# Spring2020V1_3.net
KiCad netlist of a schematic drawn in EAGLE
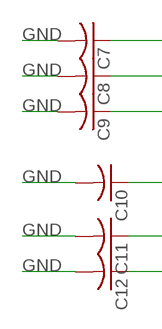
[diagram p0: schematic, sheet 1, part 1 of 2]
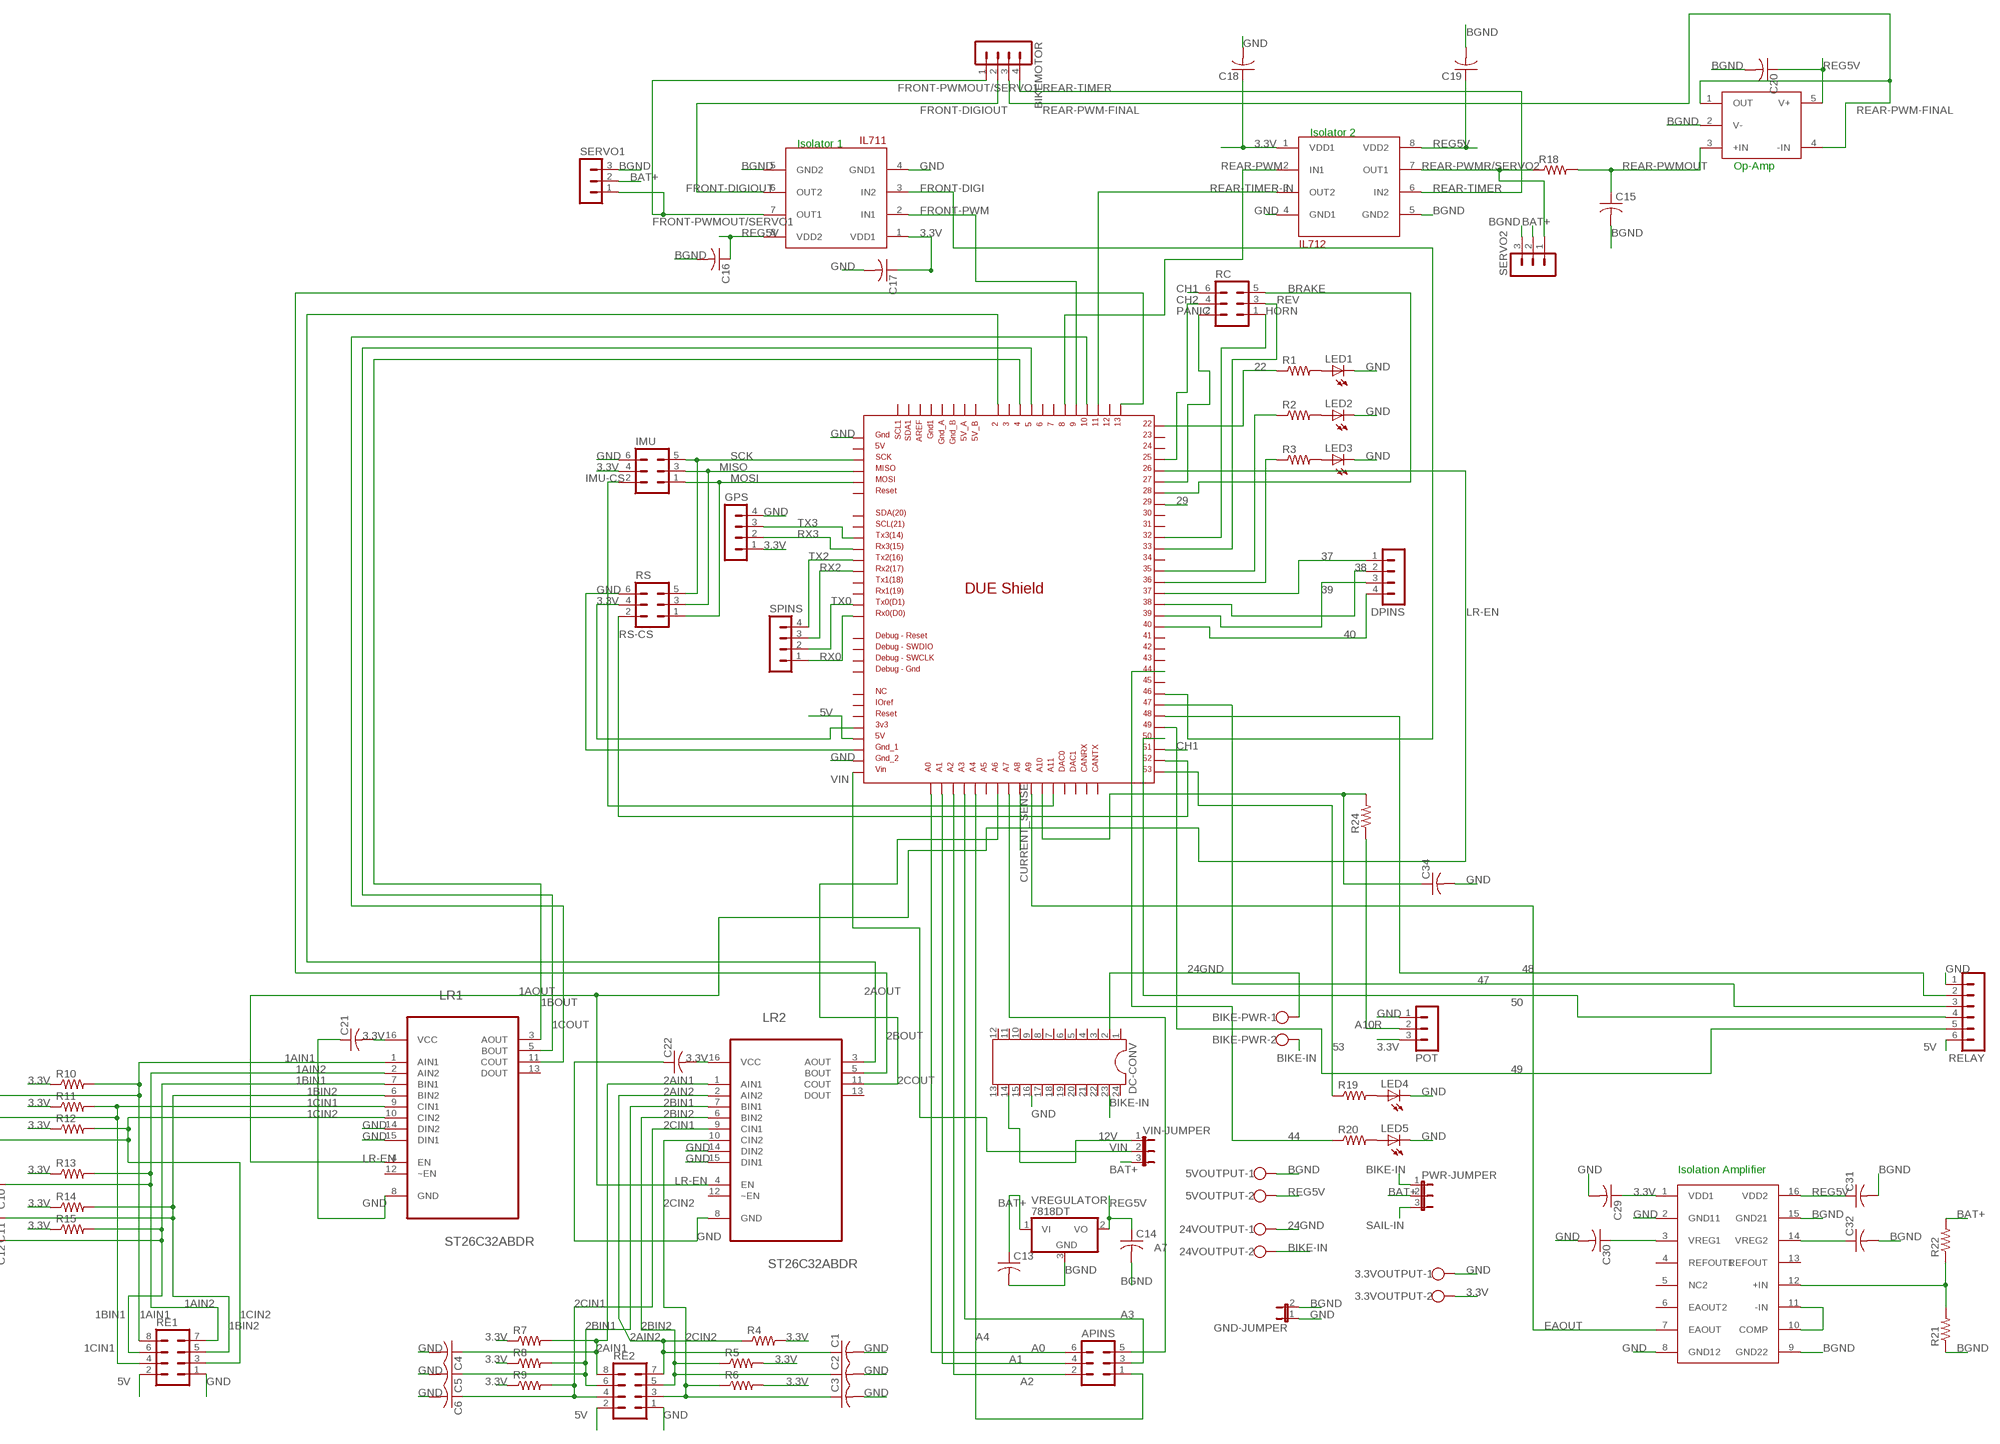
[diagram p1: schematic, sheet 1, part 2 of 2]

(export (version "E")
  (design (tool "Eeschema 10.0.6"))
  (components
    (comp (ref "3.3VOUTPUT")
      (value "W237-102")
      (footprint "eagle-import:W237-102")
      (fields (field (name "MPN") "237-102"))
      (libsource (lib "eagle-import") (part "W237-102"))
    )
    (comp (ref "5VOUTPUT")
      (value "W237-102")
      (footprint "eagle-import:W237-102")
      (fields (field (name "MPN") "237-102"))
      (libsource (lib "eagle-import") (part "W237-102"))
    )
    (comp (ref "24VOUTPUT")
      (value "W237-102")
      (footprint "eagle-import:W237-102")
      (fields (field (name "MPN") "237-102"))
      (libsource (lib "eagle-import") (part "W237-102"))
    )
    (comp (ref "APINS")
      (value "MA03-2")
      (footprint "eagle-import:MA03-2")
      (libsource (lib "eagle-import") (part "MA03-2"))
    )
    (comp (ref "BIKE-PWR")
      (value "W237-102")
      (footprint "eagle-import:W237-102")
      (fields (field (name "MPN") "237-102"))
      (libsource (lib "eagle-import") (part "W237-102"))
    )
    (comp (ref "BIKEMOTOR")
      (value "MA04-1")
      (footprint "eagle-import:MA04-1")
      (libsource (lib "eagle-import") (part "MA04-1"))
    )
    (comp (ref "C1")
      (value "C-US025-025X050")
      (footprint "eagle-import:C025-025X050")
      (libsource (lib "eagle-import") (part "C-US025-025X050"))
    )
    (comp (ref "C2")
      (value "C-US025-025X050")
      (footprint "eagle-import:C025-025X050")
      (libsource (lib "eagle-import") (part "C-US025-025X050"))
    )
    (comp (ref "C3")
      (value "C-US025-025X050")
      (footprint "eagle-import:C025-025X050")
      (libsource (lib "eagle-import") (part "C-US025-025X050"))
    )
    (comp (ref "C4")
      (value "C-US025-025X050")
      (footprint "eagle-import:C025-025X050")
      (libsource (lib "eagle-import") (part "C-US025-025X050"))
    )
    (comp (ref "C5")
      (value "C-US025-025X050")
      (footprint "eagle-import:C025-025X050")
      (libsource (lib "eagle-import") (part "C-US025-025X050"))
    )
    (comp (ref "C6")
      (value "C-US025-025X050")
      (footprint "eagle-import:C025-025X050")
      (libsource (lib "eagle-import") (part "C-US025-025X050"))
    )
    (comp (ref "C7")
      (value "C-US025-025X050")
      (footprint "eagle-import:C025-025X050")
      (libsource (lib "eagle-import") (part "C-US025-025X050"))
    )
    (comp (ref "C8")
      (value "C-US025-025X050")
      (footprint "eagle-import:C025-025X050")
      (libsource (lib "eagle-import") (part "C-US025-025X050"))
    )
    (comp (ref "C9")
      (value "C-US025-025X050")
      (footprint "eagle-import:C025-025X050")
      (libsource (lib "eagle-import") (part "C-US025-025X050"))
    )
    (comp (ref "C10")
      (value "C-US025-025X050")
      (footprint "eagle-import:C025-025X050")
      (libsource (lib "eagle-import") (part "C-US025-025X050"))
    )
    (comp (ref "C11")
      (value "C-US025-025X050")
      (footprint "eagle-import:C025-025X050")
      (libsource (lib "eagle-import") (part "C-US025-025X050"))
    )
    (comp (ref "C12")
      (value "C-US025-025X050")
      (footprint "eagle-import:C025-025X050")
      (libsource (lib "eagle-import") (part "C-US025-025X050"))
    )
    (comp (ref "C13")
      (value "C-US025-050X050")
      (footprint "eagle-import:C025-050X050")
      (libsource (lib "eagle-import") (part "C-US025-050X050"))
    )
    (comp (ref "C14")
      (value "C-US025-050X050")
      (footprint "eagle-import:C025-050X050")
      (libsource (lib "eagle-import") (part "C-US025-050X050"))
    )
    (comp (ref "C15")
      (value "C-US025-050X050")
      (footprint "eagle-import:C025-050X050")
      (libsource (lib "eagle-import") (part "C-US025-050X050"))
    )
    (comp (ref "C16")
      (value "C-US025-050X050")
      (footprint "eagle-import:C025-050X050")
      (libsource (lib "eagle-import") (part "C-US025-050X050"))
    )
    (comp (ref "C17")
      (value "C-US025-050X050")
      (footprint "eagle-import:C025-050X050")
      (libsource (lib "eagle-import") (part "C-US025-050X050"))
    )
    (comp (ref "C18")
      (value "C-US025-050X050")
      (footprint "eagle-import:C025-050X050")
      (libsource (lib "eagle-import") (part "C-US025-050X050"))
    )
    (comp (ref "C19")
      (value "C-US025-050X050")
      (footprint "eagle-import:C025-050X050")
      (libsource (lib "eagle-import") (part "C-US025-050X050"))
    )
    (comp (ref "C20")
      (value "C-US025-050X050")
      (footprint "eagle-import:C025-050X050")
      (libsource (lib "eagle-import") (part "C-US025-050X050"))
    )
    (comp (ref "C21")
      (value "C-US025-050X050")
      (footprint "eagle-import:C025-050X050")
      (libsource (lib "eagle-import") (part "C-US025-050X050"))
    )
    (comp (ref "C22")
      (value "C-US025-050X050")
      (footprint "eagle-import:C025-050X050")
      (libsource (lib "eagle-import") (part "C-US025-050X050"))
    )
    (comp (ref "C29")
      (value "C-US025-050X050")
      (footprint "eagle-import:C025-050X050")
      (libsource (lib "eagle-import") (part "C-US025-050X050"))
    )
    (comp (ref "C30")
      (value "C-US025-050X050")
      (footprint "eagle-import:C025-050X050")
      (libsource (lib "eagle-import") (part "C-US025-050X050"))
    )
    (comp (ref "C31")
      (value "C-US025-050X050")
      (footprint "eagle-import:C025-050X050")
      (libsource (lib "eagle-import") (part "C-US025-050X050"))
    )
    (comp (ref "C32")
      (value "C-US025-050X050")
      (footprint "eagle-import:C025-050X050")
      (libsource (lib "eagle-import") (part "C-US025-050X050"))
    )
    (comp (ref "C34")
      (value "C-US025-050X050")
      (footprint "eagle-import:C025-050X050")
      (libsource (lib "eagle-import") (part "C-US025-050X050"))
    )
    (comp (ref "DC-CONV")
      (value "CU.INC---VAWQ6-Q48-S12H-6")
      (footprint "eagle-import:DIL24-6")
      (libsource (lib "eagle-import") (part "CU.INC---VAWQ6-Q48-S12H-6"))
    )
    (comp (ref "DPINS")
      (value "MA04-1")
      (footprint "eagle-import:MA04-1")
      (libsource (lib "eagle-import") (part "MA04-1"))
    )
    (comp (ref "GND-JUMPER")
      (value "JP1E")
      (footprint "eagle-import:JP1")
      (libsource (lib "eagle-import") (part "JP1E"))
    )
    (comp (ref "GPS")
      (value "MA04-1")
      (footprint "eagle-import:MA04-1")
      (libsource (lib "eagle-import") (part "MA04-1"))
    )
    (comp (ref "IMU")
      (value "MA03-2")
      (footprint "eagle-import:MA03-2")
      (libsource (lib "eagle-import") (part "MA03-2"))
    )
    (comp (ref "LED1")
      (value "LED5MM")
      (footprint "eagle-import:LED5MM")
      (libsource (lib "eagle-import") (part "LED5MM"))
    )
    (comp (ref "LED2")
      (value "LED5MM")
      (footprint "eagle-import:LED5MM")
      (libsource (lib "eagle-import") (part "LED5MM"))
    )
    (comp (ref "LED3")
      (value "LED5MM")
      (footprint "eagle-import:LED5MM")
      (libsource (lib "eagle-import") (part "LED5MM"))
    )
    (comp (ref "LED4")
      (value "LED5MM")
      (footprint "eagle-import:LED5MM")
      (libsource (lib "eagle-import") (part "LED5MM"))
    )
    (comp (ref "LED5")
      (value "LED5MM")
      (footprint "eagle-import:LED5MM")
      (libsource (lib "eagle-import") (part "LED5MM"))
    )
    (comp (ref "LR1")
      (value "ST26C32ABDR")
      (footprint "eagle-import:SOIC127P600X175-16N")
      (libsource (lib "eagle-import") (part "ST26C32ABDR"))
    )
    (comp (ref "LR2")
      (value "ST26C32ABDR")
      (footprint "eagle-import:SOIC127P600X175-16N")
      (libsource (lib "eagle-import") (part "ST26C32ABDR"))
    )
    (comp (ref "OP-AMP")
      (value "OPAMP")
      (footprint "eagle-import:SOT95P280X145-5N")
      (libsource (lib "eagle-import") (part "OPAMP"))
    )
    (comp (ref "POT")
      (value "MA03-1")
      (footprint "eagle-import:MA03-1")
      (libsource (lib "eagle-import") (part "MA03-1"))
    )
    (comp (ref "PWR-JUMPER")
      (value "JP2E")
      (footprint "eagle-import:JP2")
      (libsource (lib "eagle-import") (part "JP2E"))
    )
    (comp (ref "R1")
      (value "R-US_0309/10")
      (footprint "eagle-import:0309_10")
      (libsource (lib "eagle-import") (part "R-US_0309/10"))
    )
    (comp (ref "R2")
      (value "R-US_0309/10")
      (footprint "eagle-import:0309_10")
      (libsource (lib "eagle-import") (part "R-US_0309/10"))
    )
    (comp (ref "R3")
      (value "R-US_0309/10")
      (footprint "eagle-import:0309_10")
      (libsource (lib "eagle-import") (part "R-US_0309/10"))
    )
    (comp (ref "R4")
      (value "R-US_0613/15")
      (footprint "eagle-import:P0613_15")
      (libsource (lib "eagle-import") (part "resistor_R-US_0613/15"))
    )
    (comp (ref "R5")
      (value "R-US_0613/15")
      (footprint "eagle-import:P0613_15")
      (libsource (lib "eagle-import") (part "resistor_R-US_0613/15"))
    )
    (comp (ref "R6")
      (value "R-US_0613/15")
      (footprint "eagle-import:P0613_15")
      (libsource (lib "eagle-import") (part "resistor_R-US_0613/15"))
    )
    (comp (ref "R7")
      (value "R-US_0613/15")
      (footprint "eagle-import:P0613_15")
      (libsource (lib "eagle-import") (part "resistor_R-US_0613/15"))
    )
    (comp (ref "R8")
      (value "R-US_0613/15")
      (footprint "eagle-import:P0613_15")
      (libsource (lib "eagle-import") (part "resistor_R-US_0613/15"))
    )
    (comp (ref "R9")
      (value "R-US_0613/15")
      (footprint "eagle-import:P0613_15")
      (libsource (lib "eagle-import") (part "resistor_R-US_0613/15"))
    )
    (comp (ref "R10")
      (value "R-US_0613/15")
      (footprint "eagle-import:P0613_15")
      (libsource (lib "eagle-import") (part "resistor_R-US_0613/15"))
    )
    (comp (ref "R11")
      (value "R-US_0613/15")
      (footprint "eagle-import:P0613_15")
      (libsource (lib "eagle-import") (part "resistor_R-US_0613/15"))
    )
    (comp (ref "R12")
      (value "R-US_0613/15")
      (footprint "eagle-import:P0613_15")
      (libsource (lib "eagle-import") (part "resistor_R-US_0613/15"))
    )
    (comp (ref "R13")
      (value "R-US_0613/15")
      (footprint "eagle-import:P0613_15")
      (libsource (lib "eagle-import") (part "resistor_R-US_0613/15"))
    )
    (comp (ref "R14")
      (value "R-US_0613/15")
      (footprint "eagle-import:P0613_15")
      (libsource (lib "eagle-import") (part "resistor_R-US_0613/15"))
    )
    (comp (ref "R15")
      (value "R-US_0613/15")
      (footprint "eagle-import:P0613_15")
      (libsource (lib "eagle-import") (part "resistor_R-US_0613/15"))
    )
    (comp (ref "R18")
      (value "R-US_0414/15")
      (footprint "eagle-import:0414_15")
      (libsource (lib "eagle-import") (part "resistor_R-US_0414/15"))
    )
    (comp (ref "R19")
      (value "R-US_0309/10")
      (footprint "eagle-import:0309_10")
      (libsource (lib "eagle-import") (part "R-US_0309/10"))
    )
    (comp (ref "R20")
      (value "R-US_0309/10")
      (footprint "eagle-import:0309_10")
      (libsource (lib "eagle-import") (part "R-US_0309/10"))
    )
    (comp (ref "R21")
      (value "R-US_0414/15")
      (footprint "eagle-import:0414_15")
      (libsource (lib "eagle-import") (part "resistor_R-US_0414/15"))
    )
    (comp (ref "R22")
      (value "R-US_0414/15")
      (footprint "eagle-import:0414_15")
      (libsource (lib "eagle-import") (part "resistor_R-US_0414/15"))
    )
    (comp (ref "R24")
      (value "R-US_0414/15")
      (footprint "eagle-import:0414_15")
      (libsource (lib "eagle-import") (part "resistor_R-US_0414/15"))
    )
    (comp (ref "RC")
      (value "MA03-2")
      (footprint "eagle-import:MA03-2")
      (libsource (lib "eagle-import") (part "MA03-2"))
    )
    (comp (ref "RE1")
      (value "MA04-2")
      (footprint "eagle-import:MA04-2")
      (libsource (lib "eagle-import") (part "MA04-2"))
    )
    (comp (ref "RE2")
      (value "MA04-2")
      (footprint "eagle-import:MA04-2")
      (libsource (lib "eagle-import") (part "MA04-2"))
    )
    (comp (ref "RELAY")
      (value "MA06-1")
      (footprint "eagle-import:MA06-1")
      (libsource (lib "eagle-import") (part "MA06-1"))
    )
    (comp (ref "RS")
      (value "MA03-2")
      (footprint "eagle-import:MA03-2")
      (libsource (lib "eagle-import") (part "MA03-2"))
    )
    (comp (ref "SERVO1")
      (value "MA03-1")
      (footprint "eagle-import:MA03-1")
      (libsource (lib "eagle-import") (part "MA03-1"))
    )
    (comp (ref "SERVO2")
      (value "MA03-1")
      (footprint "eagle-import:MA03-1")
      (libsource (lib "eagle-import") (part "MA03-1"))
    )
    (comp (ref "SPINS")
      (value "MA04-1")
      (footprint "eagle-import:MA04-1")
      (libsource (lib "eagle-import") (part "MA04-1"))
    )
    (comp (ref "U$1")
      (value "DUE(NORMAL)")
      (footprint "eagle-import:DUE(NORMAL)")
      (libsource (lib "eagle-import") (part "DUE(NORMAL)"))
    )
    (comp (ref "U$2")
      (value "IL-711")
      (footprint "eagle-import:8PINSOIC")
      (libsource (lib "eagle-import") (part "IL-711"))
    )
    (comp (ref "U$5")
      (value "ISOLATED_ERROR_AMP_ADUM3190")
      (footprint "eagle-import:QSOP16")
      (libsource (lib "eagle-import") (part "ISOLATED_ERROR_AMP_ADUM3190"))
    )
    (comp (ref "U$7")
      (value "IL-712")
      (footprint "eagle-import:8PINSOIC")
      (libsource (lib "eagle-import") (part "IL-712"))
    )
    (comp (ref "VIN-JUMPER")
      (value "JP2E")
      (footprint "eagle-import:JP2")
      (libsource (lib "eagle-import") (part "JP2E"))
    )
    (comp (ref "VREGULATOR")
      (value "7818DT")
      (footprint "eagle-import:TO252")
      (libsource (lib "eagle-import") (part "78DT18"))
    )
  )
  (nets
    (net (code "1") (name "/1AIN1") (class "Default")
      (node (ref "C7") (pin "1") (pinfunction "1_1") (pintype "passive"))
      (node (ref "LR1") (pin "1") (pinfunction "AIN1_1") (pintype "input"))
      (node (ref "R10") (pin "2") (pinfunction "2_2") (pintype "passive"))
      (node (ref "RE1") (pin "8") (pinfunction "8_8") (pintype "passive"))
    )
    (net (code "2") (name "/1AIN2") (class "Default")
      (node (ref "C10") (pin "1") (pinfunction "1_1") (pintype "passive"))
      (node (ref "LR1") (pin "2") (pinfunction "AIN2_2") (pintype "input"))
      (node (ref "R13") (pin "2") (pinfunction "2_2") (pintype "passive"))
      (node (ref "RE1") (pin "7") (pinfunction "7_7") (pintype "passive"))
    )
    (net (code "3") (name "/1AOUT") (class "Default")
      (node (ref "LR1") (pin "3") (pinfunction "AOUT_3") (pintype "output"))
      (node (ref "U$1") (pin "4") (pinfunction "4_4") (pintype "bidirectional"))
    )
    (net (code "4") (name "/1BIN1") (class "Default")
      (node (ref "C12") (pin "1") (pinfunction "1_1") (pintype "passive"))
      (node (ref "LR1") (pin "7") (pinfunction "BIN1_7") (pintype "input"))
      (node (ref "R15") (pin "2") (pinfunction "2_2") (pintype "passive"))
      (node (ref "RE1") (pin "6") (pinfunction "6_6") (pintype "passive"))
    )
    (net (code "5") (name "/1BIN2") (class "Default")
      (node (ref "C11") (pin "1") (pinfunction "1_1") (pintype "passive"))
      (node (ref "LR1") (pin "6") (pinfunction "BIN2_6") (pintype "input"))
      (node (ref "R14") (pin "2") (pinfunction "2_2") (pintype "passive"))
      (node (ref "RE1") (pin "5") (pinfunction "5_5") (pintype "passive"))
    )
    (net (code "6") (name "/1BOUT") (class "Default")
      (node (ref "LR1") (pin "5") (pinfunction "BOUT_5") (pintype "output"))
      (node (ref "U$1") (pin "5") (pinfunction "5_5") (pintype "bidirectional"))
    )
    (net (code "7") (name "/1CIN1") (class "Default")
      (node (ref "C8") (pin "1") (pinfunction "1_1") (pintype "passive"))
      (node (ref "LR1") (pin "9") (pinfunction "CIN1_9") (pintype "input"))
      (node (ref "R11") (pin "2") (pinfunction "2_2") (pintype "passive"))
      (node (ref "RE1") (pin "4") (pinfunction "4_4") (pintype "passive"))
    )
    (net (code "8") (name "/1CIN2") (class "Default")
      (node (ref "C9") (pin "1") (pinfunction "1_1") (pintype "passive"))
      (node (ref "LR1") (pin "10") (pinfunction "CIN2_10") (pintype "input"))
      (node (ref "R12") (pin "2") (pinfunction "2_2") (pintype "passive"))
      (node (ref "RE1") (pin "3") (pinfunction "3_3") (pintype "passive"))
    )
    (net (code "9") (name "/1COUT") (class "Default")
      (node (ref "LR1") (pin "11") (pinfunction "COUT_11") (pintype "output"))
      (node (ref "U$1") (pin "10") (pinfunction "10_10") (pintype "bidirectional"))
    )
    (net (code "10") (name "/2AIN1") (class "Default")
      (node (ref "C4") (pin "1") (pinfunction "1_1") (pintype "passive"))
      (node (ref "LR2") (pin "1") (pinfunction "AIN1_1") (pintype "input"))
      (node (ref "R7") (pin "2") (pinfunction "2_2") (pintype "passive"))
      (node (ref "RE2") (pin "8") (pinfunction "8_8") (pintype "passive"))
    )
    (net (code "11") (name "/2AIN2") (class "Default")
      (node (ref "C1") (pin "1") (pinfunction "1_1") (pintype "passive"))
      (node (ref "LR2") (pin "2") (pinfunction "AIN2_2") (pintype "input"))
      (node (ref "R4") (pin "1") (pinfunction "1_1") (pintype "passive"))
      (node (ref "RE2") (pin "7") (pinfunction "7_7") (pintype "passive"))
    )
    (net (code "12") (name "/2AOUT") (class "Default")
      (node (ref "LR2") (pin "3") (pinfunction "AOUT_3") (pintype "output"))
      (node (ref "U$1") (pin "2") (pinfunction "2_2") (pintype "bidirectional"))
    )
    (net (code "13") (name "/2BIN1") (class "Default")
      (node (ref "C5") (pin "1") (pinfunction "1_1") (pintype "passive"))
      (node (ref "LR2") (pin "7") (pinfunction "BIN1_7") (pintype "input"))
      (node (ref "R8") (pin "2") (pinfunction "2_2") (pintype "passive"))
      (node (ref "RE2") (pin "6") (pinfunction "6_6") (pintype "passive"))
    )
    (net (code "14") (name "/2BIN2") (class "Default")
      (node (ref "C2") (pin "1") (pinfunction "1_1") (pintype "passive"))
      (node (ref "LR2") (pin "6") (pinfunction "BIN2_6") (pintype "input"))
      (node (ref "R5") (pin "1") (pinfunction "1_1") (pintype "passive"))
      (node (ref "RE2") (pin "5") (pinfunction "5_5") (pintype "passive"))
    )
    (net (code "15") (name "/2BOUT") (class "Default")
      (node (ref "LR2") (pin "5") (pinfunction "BOUT_5") (pintype "output"))
      (node (ref "U$1") (pin "13") (pinfunction "13_13") (pintype "bidirectional"))
    )
    (net (code "16") (name "/2CIN1") (class "Default")
      (node (ref "C6") (pin "1") (pinfunction "1_1") (pintype "passive"))
      (node (ref "LR2") (pin "9") (pinfunction "CIN1_9") (pintype "input"))
      (node (ref "R9") (pin "2") (pinfunction "2_2") (pintype "passive"))
      (node (ref "RE2") (pin "4") (pinfunction "4_4") (pintype "passive"))
    )
    (net (code "17") (name "/2CIN2") (class "Default")
      (node (ref "C3") (pin "1") (pinfunction "1_1") (pintype "passive"))
      (node (ref "LR2") (pin "10") (pinfunction "CIN2_10") (pintype "input"))
      (node (ref "R6") (pin "1") (pinfunction "1_1") (pintype "passive"))
      (node (ref "RE2") (pin "3") (pinfunction "3_3") (pintype "passive"))
    )
    (net (code "18") (name "/2COUT") (class "Default")
      (node (ref "LR2") (pin "11") (pinfunction "COUT_11") (pintype "output"))
      (node (ref "U$1") (pin "A6") (pinfunction "A6_A6") (pintype "bidirectional"))
    )
    (net (code "19") (name "/3.3V") (class "Default")
      (node (ref "3.3VOUTPUT") (pin "2") (pinfunction "KL_2") (pintype "passive"))
      (node (ref "C17") (pin "1") (pinfunction "1_1") (pintype "passive"))
      (node (ref "C18") (pin "1") (pinfunction "1_1") (pintype "passive"))
      (node (ref "C21") (pin "2") (pinfunction "2_2") (pintype "passive"))
      (node (ref "C22") (pin "2") (pinfunction "2_2") (pintype "passive"))
      (node (ref "C29") (pin "1") (pinfunction "1_1") (pintype "passive"))
      (node (ref "GPS") (pin "1") (pinfunction "1_1") (pintype "passive"))
      (node (ref "IMU") (pin "4") (pinfunction "4_4") (pintype "passive"))
      (node (ref "LR1") (pin "16") (pinfunction "VCC_16") (pintype "power_in"))
      (node (ref "LR2") (pin "16") (pinfunction "VCC_16") (pintype "power_in"))
      (node (ref "POT") (pin "3") (pinfunction "3_3") (pintype "passive"))
      (node (ref "R10") (pin "1") (pinfunction "1_1") (pintype "passive"))
      (node (ref "R11") (pin "1") (pinfunction "1_1") (pintype "passive"))
      (node (ref "R12") (pin "1") (pinfunction "1_1") (pintype "passive"))
      (node (ref "R13") (pin "1") (pinfunction "1_1") (pintype "passive"))
      (node (ref "R14") (pin "1") (pinfunction "1_1") (pintype "passive"))
      (node (ref "R15") (pin "1") (pinfunction "1_1") (pintype "passive"))
      (node (ref "R4") (pin "2") (pinfunction "2_2") (pintype "passive"))
      (node (ref "R5") (pin "2") (pinfunction "2_2") (pintype "passive"))
      (node (ref "R6") (pin "2") (pinfunction "2_2") (pintype "passive"))
      (node (ref "R7") (pin "1") (pinfunction "1_1") (pintype "passive"))
      (node (ref "R8") (pin "1") (pinfunction "1_1") (pintype "passive"))
      (node (ref "R9") (pin "1") (pinfunction "1_1") (pintype "passive"))
      (node (ref "RS") (pin "4") (pinfunction "4_4") (pintype "passive"))
      (node (ref "U$1") (pin "3V3") (pinfunction "3V3_3V3") (pintype "bidirectional"))
      (node (ref "U$2") (pin "1") (pinfunction "VDD1_1") (pintype "power_in"))
      (node (ref "U$5") (pin "1") (pinfunction "VDD1_1") (pintype "bidirectional"))
      (node (ref "U$7") (pin "1") (pinfunction "VDD1_1") (pintype "power_in"))
    )
    (net (code "20") (name "/5V") (class "Default")
      (node (ref "RE1") (pin "2") (pinfunction "2_2") (pintype "passive"))
      (node (ref "RE2") (pin "2") (pinfunction "2_2") (pintype "passive"))
      (node (ref "RELAY") (pin "6") (pinfunction "6_6") (pintype "passive"))
      (node (ref "U$1") (pin "5V") (pinfunction "5V_5V") (pintype "bidirectional"))
    )
    (net (code "21") (name "/12V") (class "Default")
      (node (ref "DC-CONV") (pin "14") (pinfunction "14_14") (pintype "passive"))
      (node (ref "VIN-JUMPER") (pin "1") (pinfunction "1_1") (pintype "passive"))
    )
    (net (code "22") (name "/22") (class "Default")
      (node (ref "R1") (pin "1") (pinfunction "1_1") (pintype "passive"))
      (node (ref "U$1") (pin "22") (pinfunction "22_22") (pintype "bidirectional"))
    )
    (net (code "23") (name "/24GND") (class "Default")
      (node (ref "24VOUTPUT") (pin "1") (pinfunction "KL_1") (pintype "passive"))
      (node (ref "BIKE-PWR") (pin "1") (pinfunction "KL_1") (pintype "passive"))
      (node (ref "DC-CONV") (pin "2") (pinfunction "2_2") (pintype "passive"))
    )
    (net (code "24") (name "/29") (class "Default")
      (node (ref "U$1") (pin "29") (pinfunction "29_29") (pintype "bidirectional"))
    )
    (net (code "25") (name "/37") (class "Default")
      (node (ref "DPINS") (pin "1") (pinfunction "1_1") (pintype "passive"))
      (node (ref "U$1") (pin "37") (pinfunction "37_37") (pintype "bidirectional"))
    )
    (net (code "26") (name "/38") (class "Default")
      (node (ref "DPINS") (pin "2") (pinfunction "2_2") (pintype "passive"))
      (node (ref "U$1") (pin "38") (pinfunction "38_38") (pintype "bidirectional"))
    )
    (net (code "27") (name "/39") (class "Default")
      (node (ref "DPINS") (pin "3") (pinfunction "3_3") (pintype "passive"))
      (node (ref "U$1") (pin "39") (pinfunction "39_39") (pintype "bidirectional"))
    )
    (net (code "28") (name "/40") (class "Default")
      (node (ref "DPINS") (pin "4") (pinfunction "4_4") (pintype "passive"))
      (node (ref "U$1") (pin "40") (pinfunction "40_40") (pintype "bidirectional"))
    )
    (net (code "29") (name "/44") (class "Default")
      (node (ref "R20") (pin "1") (pinfunction "1_1") (pintype "passive"))
      (node (ref "U$1") (pin "44") (pinfunction "44_44") (pintype "bidirectional"))
    )
    (net (code "30") (name "/47") (class "Default")
      (node (ref "RELAY") (pin "3") (pinfunction "3_3") (pintype "passive"))
      (node (ref "U$1") (pin "47") (pinfunction "47_47") (pintype "bidirectional"))
    )
    (net (code "31") (name "/48") (class "Default")
      (node (ref "RELAY") (pin "2") (pinfunction "2_2") (pintype "passive"))
      (node (ref "U$1") (pin "48") (pinfunction "48_48") (pintype "bidirectional"))
    )
    (net (code "32") (name "/49") (class "Default")
      (node (ref "RELAY") (pin "5") (pinfunction "5_5") (pintype "passive"))
      (node (ref "U$1") (pin "49") (pinfunction "49_49") (pintype "bidirectional"))
    )
    (net (code "33") (name "/50") (class "Default")
      (node (ref "RELAY") (pin "4") (pinfunction "4_4") (pintype "passive"))
      (node (ref "U$1") (pin "50") (pinfunction "50_50") (pintype "bidirectional"))
    )
    (net (code "34") (name "/53") (class "Default")
      (node (ref "R19") (pin "1") (pinfunction "1_1") (pintype "passive"))
      (node (ref "U$1") (pin "53") (pinfunction "53_53") (pintype "bidirectional"))
    )
    (net (code "35") (name "/A0") (class "Default")
      (node (ref "APINS") (pin "6") (pinfunction "6_6") (pintype "passive"))
      (node (ref "U$1") (pin "A0") (pinfunction "A0_A0") (pintype "bidirectional"))
    )
    (net (code "36") (name "/A1") (class "Default")
      (node (ref "APINS") (pin "4") (pinfunction "4_4") (pintype "passive"))
      (node (ref "U$1") (pin "A1") (pinfunction "A1_A1") (pintype "bidirectional"))
    )
    (net (code "37") (name "/A2") (class "Default")
      (node (ref "APINS") (pin "2") (pinfunction "2_2") (pintype "passive"))
      (node (ref "U$1") (pin "A2") (pinfunction "A2_A2") (pintype "bidirectional"))
    )
    (net (code "38") (name "/A3") (class "Default")
      (node (ref "APINS") (pin "3") (pinfunction "3_3") (pintype "passive"))
      (node (ref "U$1") (pin "A3") (pinfunction "A3_A3") (pintype "bidirectional"))
    )
    (net (code "39") (name "/A4") (class "Default")
      (node (ref "APINS") (pin "1") (pinfunction "1_1") (pintype "passive"))
      (node (ref "U$1") (pin "A4") (pinfunction "A4_A4") (pintype "bidirectional"))
    )
    (net (code "40") (name "/A7") (class "Default")
      (node (ref "APINS") (pin "5") (pinfunction "5_5") (pintype "passive"))
      (node (ref "U$1") (pin "A7") (pinfunction "A7_A7") (pintype "bidirectional"))
    )
    (net (code "41") (name "/A10R") (class "Default")
      (node (ref "POT") (pin "2") (pinfunction "2_2") (pintype "passive"))
      (node (ref "R24") (pin "1") (pinfunction "1_1") (pintype "passive"))
    )
    (net (code "42") (name "/BAT+") (class "Default")
      (node (ref "C13") (pin "1") (pinfunction "1_1") (pintype "passive"))
      (node (ref "PWR-JUMPER") (pin "2") (pinfunction "2_2") (pintype "passive"))
      (node (ref "R22") (pin "2") (pinfunction "2_2") (pintype "passive"))
      (node (ref "SERVO1") (pin "2") (pinfunction "2_2") (pintype "passive"))
      (node (ref "SERVO2") (pin "2") (pinfunction "2_2") (pintype "passive"))
      (node (ref "VIN-JUMPER") (pin "3") (pinfunction "3_3") (pintype "passive"))
      (node (ref "VREGULATOR") (pin "1") (pinfunction "VI_1") (pintype "input"))
    )
    (net (code "43") (name "/BGND") (class "Default")
      (node (ref "5VOUTPUT") (pin "1") (pinfunction "KL_1") (pintype "passive"))
      (node (ref "C13") (pin "2") (pinfunction "2_2") (pintype "passive"))
      (node (ref "C14") (pin "2") (pinfunction "2_2") (pintype "passive"))
      (node (ref "C15") (pin "2") (pinfunction "2_2") (pintype "passive"))
      (node (ref "C16") (pin "2") (pinfunction "2_2") (pintype "passive"))
      (node (ref "C19") (pin "2") (pinfunction "2_2") (pintype "passive"))
      (node (ref "C20") (pin "2") (pinfunction "2_2") (pintype "passive"))
      (node (ref "C31") (pin "2") (pinfunction "2_2") (pintype "passive"))
      (node (ref "C32") (pin "2") (pinfunction "2_2") (pintype "passive"))
      (node (ref "GND-JUMPER") (pin "2") (pinfunction "2_2") (pintype "passive"))
      (node (ref "OP-AMP") (pin "2") (pinfunction "V-_2") (pintype "output"))
      (node (ref "R21") (pin "1") (pinfunction "1_1") (pintype "passive"))
      (node (ref "SERVO1") (pin "3") (pinfunction "3_3") (pintype "passive"))
      (node (ref "SERVO2") (pin "3") (pinfunction "3_3") (pintype "passive"))
      (node (ref "U$2") (pin "5") (pinfunction "GND2_5") (pintype "power_in"))
      (node (ref "U$5") (pin "15") (pinfunction "GND21_15") (pintype "bidirectional"))
      (node (ref "U$5") (pin "9") (pinfunction "GND22_9") (pintype "bidirectional"))
      (node (ref "U$7") (pin "5") (pinfunction "GND2_5") (pintype "power_in"))
      (node (ref "VREGULATOR") (pin "3") (pinfunction "GND_3") (pintype "passive"))
    )
    (net (code "44") (name "/BIKE-IN") (class "Default")
      (node (ref "24VOUTPUT") (pin "2") (pinfunction "KL_2") (pintype "passive"))
      (node (ref "BIKE-PWR") (pin "2") (pinfunction "KL_2") (pintype "passive"))
      (node (ref "DC-CONV") (pin "23") (pinfunction "23_23") (pintype "passive"))
      (node (ref "PWR-JUMPER") (pin "1") (pinfunction "1_1") (pintype "passive"))
    )
    (net (code "45") (name "/BRAKE") (class "Default")
      (node (ref "RC") (pin "5") (pinfunction "5_5") (pintype "passive"))
      (node (ref "U$1") (pin "28") (pinfunction "28_28") (pintype "bidirectional"))
    )
    (net (code "46") (name "/CH1") (class "Default")
      (node (ref "RC") (pin "6") (pinfunction "6_6") (pintype "passive"))
      (node (ref "U$1") (pin "51") (pinfunction "51_51") (pintype "bidirectional"))
    )
    (net (code "47") (name "/CH2") (class "Default")
      (node (ref "RC") (pin "4") (pinfunction "4_4") (pintype "passive"))
      (node (ref "U$1") (pin "25") (pinfunction "25_25") (pintype "bidirectional"))
    )
    (net (code "48") (name "/CURRENT_SENSE") (class "Default")
      (node (ref "U$1") (pin "A8") (pinfunction "A8_A8") (pintype "bidirectional"))
    )
    (net (code "49") (name "/EAOUT") (class "Default")
      (node (ref "U$1") (pin "A9") (pinfunction "A9_A9") (pintype "bidirectional"))
      (node (ref "U$5") (pin "7") (pinfunction "EAOUT_7") (pintype "bidirectional"))
    )
    (net (code "50") (name "/FRONT-DIGI") (class "Default")
      (node (ref "U$1") (pin "46") (pinfunction "46_46") (pintype "bidirectional"))
      (node (ref "U$2") (pin "3") (pinfunction "IN2_3") (pintype "input"))
    )
    (net (code "51") (name "/FRONT-DIGIOUT") (class "Default")
      (node (ref "BIKEMOTOR") (pin "2") (pinfunction "2_2") (pintype "passive"))
      (node (ref "U$2") (pin "6") (pinfunction "OUT2_6") (pintype "output"))
    )
    (net (code "52") (name "/FRONT-PWM") (class "Default")
      (node (ref "U$1") (pin "9") (pinfunction "9_9") (pintype "bidirectional"))
      (node (ref "U$2") (pin "2") (pinfunction "IN1_2") (pintype "input"))
    )
    (net (code "53") (name "/FRONT-PWMOUT{slash}SERVO1") (class "Default")
      (node (ref "BIKEMOTOR") (pin "1") (pinfunction "1_1") (pintype "passive"))
      (node (ref "SERVO1") (pin "1") (pinfunction "1_1") (pintype "passive"))
      (node (ref "U$2") (pin "7") (pinfunction "OUT1_7") (pintype "output"))
    )
    (net (code "54") (name "/GND") (class "Default")
      (node (ref "3.3VOUTPUT") (pin "1") (pinfunction "KL_1") (pintype "passive"))
      (node (ref "C1") (pin "2") (pinfunction "2_2") (pintype "passive"))
      (node (ref "C10") (pin "2") (pinfunction "2_2") (pintype "passive"))
      (node (ref "C11") (pin "2") (pinfunction "2_2") (pintype "passive"))
      (node (ref "C12") (pin "2") (pinfunction "2_2") (pintype "passive"))
      (node (ref "C17") (pin "2") (pinfunction "2_2") (pintype "passive"))
      (node (ref "C18") (pin "2") (pinfunction "2_2") (pintype "passive"))
      (node (ref "C2") (pin "2") (pinfunction "2_2") (pintype "passive"))
      (node (ref "C21") (pin "1") (pinfunction "1_1") (pintype "passive"))
      (node (ref "C22") (pin "1") (pinfunction "1_1") (pintype "passive"))
      (node (ref "C29") (pin "2") (pinfunction "2_2") (pintype "passive"))
      (node (ref "C3") (pin "2") (pinfunction "2_2") (pintype "passive"))
      (node (ref "C30") (pin "2") (pinfunction "2_2") (pintype "passive"))
      (node (ref "C34") (pin "2") (pinfunction "2_2") (pintype "passive"))
      (node (ref "C4") (pin "2") (pinfunction "2_2") (pintype "passive"))
      (node (ref "C5") (pin "2") (pinfunction "2_2") (pintype "passive"))
      (node (ref "C6") (pin "2") (pinfunction "2_2") (pintype "passive"))
      (node (ref "C7") (pin "2") (pinfunction "2_2") (pintype "passive"))
      (node (ref "C8") (pin "2") (pinfunction "2_2") (pintype "passive"))
      (node (ref "C9") (pin "2") (pinfunction "2_2") (pintype "passive"))
      (node (ref "DC-CONV") (pin "16") (pinfunction "16_16") (pintype "passive"))
      (node (ref "GND-JUMPER") (pin "1") (pinfunction "1_1") (pintype "passive"))
      (node (ref "GPS") (pin "4") (pinfunction "4_4") (pintype "passive"))
      (node (ref "IMU") (pin "6") (pinfunction "6_6") (pintype "passive"))
      (node (ref "LED1") (pin "K") (pinfunction "C_K") (pintype "passive"))
      (node (ref "LED2") (pin "K") (pinfunction "C_K") (pintype "passive"))
      (node (ref "LED3") (pin "K") (pinfunction "C_K") (pintype "passive"))
      (node (ref "LED4") (pin "K") (pinfunction "C_K") (pintype "passive"))
      (node (ref "LED5") (pin "K") (pinfunction "C_K") (pintype "passive"))
      (node (ref "LR1") (pin "14") (pinfunction "DIN2_14") (pintype "input"))
      (node (ref "LR1") (pin "15") (pinfunction "DIN1_15") (pintype "input"))
      (node (ref "LR1") (pin "8") (pinfunction "GND_8") (pintype "passive"))
      (node (ref "LR2") (pin "14") (pinfunction "DIN2_14") (pintype "input"))
      (node (ref "LR2") (pin "15") (pinfunction "DIN1_15") (pintype "input"))
      (node (ref "LR2") (pin "8") (pinfunction "GND_8") (pintype "passive"))
      (node (ref "POT") (pin "1") (pinfunction "1_1") (pintype "passive"))
      (node (ref "RE1") (pin "1") (pinfunction "1_1") (pintype "passive"))
      (node (ref "RE2") (pin "1") (pinfunction "1_1") (pintype "passive"))
      (node (ref "RELAY") (pin "1") (pinfunction "1_1") (pintype "passive"))
      (node (ref "RS") (pin "6") (pinfunction "6_6") (pintype "passive"))
      (node (ref "U$1") (pin "5V_ICSP") (pinfunction "5V_ICSP_5V_ICSP") (pintype "bidirectional"))
      (node (ref "U$1") (pin "GND_1") (pinfunction "GND_1_GND_1") (pintype "bidirectional"))
      (node (ref "U$1") (pin "GND_2") (pinfunction "GND_2_GND_2") (pintype "bidirectional"))
      (node (ref "U$2") (pin "4") (pinfunction "GND1_4") (pintype "power_in"))
      (node (ref "U$5") (pin "2") (pinfunction "GND11_2") (pintype "bidirectional"))
      (node (ref "U$5") (pin "8") (pinfunction "GND12_8") (pintype "bidirectional"))
      (node (ref "U$7") (pin "4") (pinfunction "GND1_4") (pintype "power_in"))
    )
    (net (code "55") (name "/HORN") (class "Default")
      (node (ref "RC") (pin "1") (pinfunction "1_1") (pintype "passive"))
      (node (ref "U$1") (pin "32") (pinfunction "32_32") (pintype "bidirectional"))
    )
    (net (code "56") (name "/IMU-CS") (class "Default")
      (node (ref "IMU") (pin "2") (pinfunction "2_2") (pintype "passive"))
      (node (ref "U$1") (pin "A11") (pinfunction "A11_A11") (pintype "bidirectional"))
    )
    (net (code "57") (name "/LR-EN") (class "Default")
      (node (ref "LR1") (pin "4") (pinfunction "EN_4") (pintype "input"))
      (node (ref "LR2") (pin "4") (pinfunction "EN_4") (pintype "input"))
      (node (ref "U$1") (pin "26") (pinfunction "26_26") (pintype "bidirectional"))
    )
    (net (code "58") (name "/MISO") (class "Default")
      (node (ref "IMU") (pin "3") (pinfunction "3_3") (pintype "passive"))
      (node (ref "RS") (pin "3") (pinfunction "3_3") (pintype "passive"))
      (node (ref "U$1") (pin "MISO_ICSP") (pinfunction "MISO_ICSP_MISO_ICSP") (pintype "bidirectional"))
    )
    (net (code "59") (name "/MOSI") (class "Default")
      (node (ref "IMU") (pin "1") (pinfunction "1_1") (pintype "passive"))
      (node (ref "RS") (pin "1") (pinfunction "1_1") (pintype "passive"))
      (node (ref "U$1") (pin "MOSI_ICSP") (pinfunction "MOSI_ICSP_MOSI_ICSP") (pintype "bidirectional"))
    )
    (net (code "60") (name "/PANIC") (class "Default")
      (node (ref "RC") (pin "2") (pinfunction "2_2") (pintype "passive"))
      (node (ref "U$1") (pin "27") (pinfunction "27_27") (pintype "bidirectional"))
    )
    (net (code "61") (name "/REAR-PWM") (class "Default")
      (node (ref "U$1") (pin "8") (pinfunction "8_8") (pintype "bidirectional"))
      (node (ref "U$7") (pin "2") (pinfunction "IN1_2") (pintype "input"))
    )
    (net (code "62") (name "/REAR-PWM-FINAL") (class "Default")
      (node (ref "BIKEMOTOR") (pin "3") (pinfunction "3_3") (pintype "passive"))
      (node (ref "OP-AMP") (pin "1") (pinfunction "OUT_1") (pintype "output"))
      (node (ref "OP-AMP") (pin "4") (pinfunction "-IN_4") (pintype "input"))
    )
    (net (code "63") (name "/REAR-PWMOUT") (class "Default")
      (node (ref "C15") (pin "1") (pinfunction "1_1") (pintype "passive"))
      (node (ref "OP-AMP") (pin "3") (pinfunction "+IN_3") (pintype "input"))
      (node (ref "R18") (pin "2") (pinfunction "2_2") (pintype "passive"))
    )
    (net (code "64") (name "/REAR-PWMR{slash}SERVO2") (class "Default")
      (node (ref "R18") (pin "1") (pinfunction "1_1") (pintype "passive"))
      (node (ref "SERVO2") (pin "1") (pinfunction "1_1") (pintype "passive"))
      (node (ref "U$7") (pin "7") (pinfunction "OUT1_7") (pintype "output"))
    )
    (net (code "65") (name "/REAR-TIMER") (class "Default")
      (node (ref "BIKEMOTOR") (pin "4") (pinfunction "4_4") (pintype "passive"))
      (node (ref "U$7") (pin "6") (pinfunction "IN2_6") (pintype "input"))
    )
    (net (code "66") (name "/REAR-TIMER-IN") (class "Default")
      (node (ref "U$1") (pin "11") (pinfunction "11_11") (pintype "bidirectional"))
      (node (ref "U$7") (pin "3") (pinfunction "OUT2_3") (pintype "output"))
    )
    (net (code "67") (name "/REG5V") (class "Default")
      (node (ref "5VOUTPUT") (pin "2") (pinfunction "KL_2") (pintype "passive"))
      (node (ref "C14") (pin "1") (pinfunction "1_1") (pintype "passive"))
      (node (ref "C16") (pin "1") (pinfunction "1_1") (pintype "passive"))
      (node (ref "C19") (pin "1") (pinfunction "1_1") (pintype "passive"))
      (node (ref "C20") (pin "1") (pinfunction "1_1") (pintype "passive"))
      (node (ref "C31") (pin "1") (pinfunction "1_1") (pintype "passive"))
      (node (ref "OP-AMP") (pin "5") (pinfunction "V+_5") (pintype "power_in"))
      (node (ref "U$2") (pin "8") (pinfunction "VDD2_8") (pintype "power_in"))
      (node (ref "U$5") (pin "16") (pinfunction "VDD2_16") (pintype "bidirectional"))
      (node (ref "U$7") (pin "8") (pinfunction "VDD2_8") (pintype "power_in"))
      (node (ref "VREGULATOR") (pin "2") (pinfunction "VO_2") (pintype "passive"))
    )
    (net (code "68") (name "/REV") (class "Default")
      (node (ref "RC") (pin "3") (pinfunction "3_3") (pintype "passive"))
      (node (ref "U$1") (pin "33") (pinfunction "33_33") (pintype "bidirectional"))
    )
    (net (code "69") (name "/RS-CS") (class "Default")
      (node (ref "RS") (pin "2") (pinfunction "2_2") (pintype "passive"))
      (node (ref "U$1") (pin "52") (pinfunction "52_52") (pintype "bidirectional"))
    )
    (net (code "70") (name "/RX0") (class "Default")
      (node (ref "SPINS") (pin "1") (pinfunction "1_1") (pintype "passive"))
      (node (ref "U$1") (pin "RX0") (pinfunction "RX0_RX0") (pintype "bidirectional"))
    )
    (net (code "71") (name "/RX2") (class "Default")
      (node (ref "SPINS") (pin "3") (pinfunction "3_3") (pintype "passive"))
      (node (ref "U$1") (pin "RX2") (pinfunction "RX2_RX2") (pintype "bidirectional"))
    )
    (net (code "72") (name "/RX3") (class "Default")
      (node (ref "GPS") (pin "2") (pinfunction "2_2") (pintype "passive"))
      (node (ref "U$1") (pin "RX3") (pinfunction "RX3_RX3") (pintype "bidirectional"))
    )
    (net (code "73") (name "/SAIL-IN") (class "Default")
      (node (ref "PWR-JUMPER") (pin "3") (pinfunction "3_3") (pintype "passive"))
    )
    (net (code "74") (name "/SCK") (class "Default")
      (node (ref "IMU") (pin "5") (pinfunction "5_5") (pintype "passive"))
      (node (ref "RS") (pin "5") (pinfunction "5_5") (pintype "passive"))
      (node (ref "U$1") (pin "SCK_ICSP") (pinfunction "SCK_ICSP_SCK_ICSP") (pintype "bidirectional"))
    )
    (net (code "75") (name "/TX0") (class "Default")
      (node (ref "SPINS") (pin "2") (pinfunction "2_2") (pintype "passive"))
      (node (ref "U$1") (pin "TX0") (pinfunction "TX0_TX0") (pintype "bidirectional"))
    )
    (net (code "76") (name "/TX2") (class "Default")
      (node (ref "SPINS") (pin "4") (pinfunction "4_4") (pintype "passive"))
      (node (ref "U$1") (pin "TX2") (pinfunction "TX2_TX2") (pintype "bidirectional"))
    )
    (net (code "77") (name "/TX3") (class "Default")
      (node (ref "GPS") (pin "3") (pinfunction "3_3") (pintype "passive"))
      (node (ref "U$1") (pin "TX3") (pinfunction "TX3_TX3") (pintype "bidirectional"))
    )
    (net (code "78") (name "/VIN") (class "Default")
      (node (ref "U$1") (pin "VIN") (pinfunction "VIN_VIN") (pintype "bidirectional"))
      (node (ref "VIN-JUMPER") (pin "2") (pinfunction "2_2") (pintype "passive"))
    )
    (net (code "79") (name "Net-(C34-Pad1)") (class "Default")
      (node (ref "C34") (pin "1") (pinfunction "1_1") (pintype "passive"))
      (node (ref "R24") (pin "2") (pinfunction "2_2") (pintype "passive"))
      (node (ref "U$1") (pin "A10") (pinfunction "A10_A10") (pintype "bidirectional"))
    )
    (net (code "80") (name "Net-(LED1-PadA)") (class "Default")
      (node (ref "LED1") (pin "A") (pinfunction "A_A") (pintype "passive"))
      (node (ref "R1") (pin "2") (pinfunction "2_2") (pintype "passive"))
    )
    (net (code "81") (name "Net-(LED2-PadA)") (class "Default")
      (node (ref "LED2") (pin "A") (pinfunction "A_A") (pintype "passive"))
      (node (ref "R2") (pin "2") (pinfunction "2_2") (pintype "passive"))
    )
    (net (code "82") (name "Net-(LED3-PadA)") (class "Default")
      (node (ref "LED3") (pin "A") (pinfunction "A_A") (pintype "passive"))
      (node (ref "R3") (pin "2") (pinfunction "2_2") (pintype "passive"))
    )
    (net (code "83") (name "Net-(LED4-PadA)") (class "Default")
      (node (ref "LED4") (pin "A") (pinfunction "A_A") (pintype "passive"))
      (node (ref "R19") (pin "2") (pinfunction "2_2") (pintype "passive"))
    )
    (net (code "84") (name "Net-(LED5-PadA)") (class "Default")
      (node (ref "LED5") (pin "A") (pinfunction "A_A") (pintype "passive"))
      (node (ref "R20") (pin "2") (pinfunction "2_2") (pintype "passive"))
    )
    (net (code "85") (name "Net-(R2-Pad1)") (class "Default")
      (node (ref "R2") (pin "1") (pinfunction "1_1") (pintype "passive"))
      (node (ref "U$1") (pin "35") (pinfunction "35_35") (pintype "bidirectional"))
    )
    (net (code "86") (name "Net-(R3-Pad1)") (class "Default")
      (node (ref "R3") (pin "1") (pinfunction "1_1") (pintype "passive"))
      (node (ref "U$1") (pin "36") (pinfunction "36_36") (pintype "bidirectional"))
    )
    (net (code "87") (name "Net-(U$5-+IN)") (class "Default")
      (node (ref "R21") (pin "2") (pinfunction "2_2") (pintype "passive"))
      (node (ref "R22") (pin "1") (pinfunction "1_1") (pintype "passive"))
      (node (ref "U$5") (pin "12") (pinfunction "+IN_12") (pintype "bidirectional"))
    )
    (net (code "88") (name "Net-(U$5--IN)") (class "Default")
      (node (ref "U$5") (pin "10") (pinfunction "COMP_10") (pintype "bidirectional"))
      (node (ref "U$5") (pin "11") (pinfunction "-IN_11") (pintype "bidirectional"))
    )
    (net (code "89") (name "Net-(U$5-VREG1)") (class "Default")
      (node (ref "C30") (pin "1") (pinfunction "1_1") (pintype "passive"))
      (node (ref "U$5") (pin "3") (pinfunction "VREG1_3") (pintype "bidirectional"))
    )
    (net (code "90") (name "Net-(U$5-VREG2)") (class "Default")
      (node (ref "C32") (pin "1") (pinfunction "1_1") (pintype "passive"))
      (node (ref "U$5") (pin "14") (pinfunction "VREG2_14") (pintype "bidirectional"))
    )
    (net (code "91") (name "unconnected-(DC-CONV-Pad1)") (class "Default")
      (node (ref "DC-CONV") (pin "1") (pinfunction "1_1") (pintype "passive"))
    )
    (net (code "92") (name "unconnected-(DC-CONV-Pad3)") (class "Default")
      (node (ref "DC-CONV") (pin "3") (pinfunction "3_3") (pintype "passive"))
    )
    (net (code "93") (name "unconnected-(DC-CONV-Pad4)") (class "Default")
      (node (ref "DC-CONV") (pin "4") (pinfunction "4_4") (pintype "passive"))
    )
    (net (code "94") (name "unconnected-(DC-CONV-Pad5)") (class "Default")
      (node (ref "DC-CONV") (pin "5") (pinfunction "5_5") (pintype "passive"))
    )
    (net (code "95") (name "unconnected-(DC-CONV-Pad6)") (class "Default")
      (node (ref "DC-CONV") (pin "6") (pinfunction "6_6") (pintype "passive"))
    )
    (net (code "96") (name "unconnected-(DC-CONV-Pad7)") (class "Default")
      (node (ref "DC-CONV") (pin "7") (pinfunction "7_7") (pintype "passive"))
    )
    (net (code "97") (name "unconnected-(DC-CONV-Pad8)") (class "Default")
      (node (ref "DC-CONV") (pin "8") (pinfunction "8_8") (pintype "passive"))
    )
    (net (code "98") (name "unconnected-(DC-CONV-Pad9)") (class "Default")
      (node (ref "DC-CONV") (pin "9") (pinfunction "9_9") (pintype "passive"))
    )
    (net (code "99") (name "unconnected-(DC-CONV-Pad10)") (class "Default")
      (node (ref "DC-CONV") (pin "10") (pinfunction "10_10") (pintype "passive"))
    )
    (net (code "100") (name "unconnected-(DC-CONV-Pad11)") (class "Default")
      (node (ref "DC-CONV") (pin "11") (pinfunction "11_11") (pintype "passive"))
    )
    (net (code "101") (name "unconnected-(DC-CONV-Pad12)") (class "Default")
      (node (ref "DC-CONV") (pin "12") (pinfunction "12_12") (pintype "passive"))
    )
    (net (code "102") (name "unconnected-(DC-CONV-Pad13)") (class "Default")
      (node (ref "DC-CONV") (pin "13") (pinfunction "13_13") (pintype "passive"))
    )
    (net (code "103") (name "unconnected-(DC-CONV-Pad15)") (class "Default")
      (node (ref "DC-CONV") (pin "15") (pinfunction "15_15") (pintype "passive"))
    )
    (net (code "104") (name "unconnected-(DC-CONV-Pad17)") (class "Default")
      (node (ref "DC-CONV") (pin "17") (pinfunction "17_17") (pintype "passive"))
    )
    (net (code "105") (name "unconnected-(DC-CONV-Pad18)") (class "Default")
      (node (ref "DC-CONV") (pin "18") (pinfunction "18_18") (pintype "passive"))
    )
    (net (code "106") (name "unconnected-(DC-CONV-Pad19)") (class "Default")
      (node (ref "DC-CONV") (pin "19") (pinfunction "19_19") (pintype "passive"))
    )
    (net (code "107") (name "unconnected-(DC-CONV-Pad20)") (class "Default")
      (node (ref "DC-CONV") (pin "20") (pinfunction "20_20") (pintype "passive"))
    )
    (net (code "108") (name "unconnected-(DC-CONV-Pad21)") (class "Default")
      (node (ref "DC-CONV") (pin "21") (pinfunction "21_21") (pintype "passive"))
    )
    (net (code "109") (name "unconnected-(DC-CONV-Pad22)") (class "Default")
      (node (ref "DC-CONV") (pin "22") (pinfunction "22_22") (pintype "passive"))
    )
    (net (code "110") (name "unconnected-(DC-CONV-Pad24)") (class "Default")
      (node (ref "DC-CONV") (pin "24") (pinfunction "24_24") (pintype "passive"))
    )
    (net (code "111") (name "unconnected-(LR1-DOUT-Pad13)") (class "Default")
      (node (ref "LR1") (pin "13") (pinfunction "DOUT_13") (pintype "output"))
    )
    (net (code "112") (name "unconnected-(LR1-~{EN}-Pad12)") (class "Default")
      (node (ref "LR1") (pin "12") (pinfunction "~{EN}_12") (pintype "input"))
    )
    (net (code "113") (name "unconnected-(LR2-DOUT-Pad13)") (class "Default")
      (node (ref "LR2") (pin "13") (pinfunction "DOUT_13") (pintype "output"))
    )
    (net (code "114") (name "unconnected-(LR2-~{EN}-Pad12)") (class "Default")
      (node (ref "LR2") (pin "12") (pinfunction "~{EN}_12") (pintype "input"))
    )
    (net (code "115") (name "unconnected-(U$1-Pad3)") (class "Default")
      (node (ref "U$1") (pin "3") (pinfunction "3_3") (pintype "bidirectional"))
    )
    (net (code "116") (name "unconnected-(U$1-Pad5V_A)") (class "Default")
      (node (ref "U$1") (pin "5V_A") (pinfunction "5V_A_5V_A") (pintype "bidirectional"))
    )
    (net (code "117") (name "unconnected-(U$1-Pad5V_B)") (class "Default")
      (node (ref "U$1") (pin "5V_B") (pinfunction "5V_B_5V_B") (pintype "bidirectional"))
    )
    (net (code "118") (name "unconnected-(U$1-Pad6)") (class "Default")
      (node (ref "U$1") (pin "6") (pinfunction "6_6") (pintype "bidirectional"))
    )
    (net (code "119") (name "unconnected-(U$1-Pad7)") (class "Default")
      (node (ref "U$1") (pin "7") (pinfunction "7_7") (pintype "bidirectional"))
    )
    (net (code "120") (name "unconnected-(U$1-Pad12)") (class "Default")
      (node (ref "U$1") (pin "12") (pinfunction "12_12") (pintype "bidirectional"))
    )
    (net (code "121") (name "unconnected-(U$1-Pad23)") (class "Default")
      (node (ref "U$1") (pin "23") (pinfunction "23_23") (pintype "bidirectional"))
    )
    (net (code "122") (name "unconnected-(U$1-Pad24)") (class "Default")
      (node (ref "U$1") (pin "24") (pinfunction "24_24") (pintype "bidirectional"))
    )
    (net (code "123") (name "unconnected-(U$1-Pad30)") (class "Default")
      (node (ref "U$1") (pin "30") (pinfunction "30_30") (pintype "bidirectional"))
    )
    (net (code "124") (name "unconnected-(U$1-Pad31)") (class "Default")
      (node (ref "U$1") (pin "31") (pinfunction "31_31") (pintype "bidirectional"))
    )
    (net (code "125") (name "unconnected-(U$1-Pad34)") (class "Default")
      (node (ref "U$1") (pin "34") (pinfunction "34_34") (pintype "bidirectional"))
    )
    (net (code "126") (name "unconnected-(U$1-Pad41)") (class "Default")
      (node (ref "U$1") (pin "41") (pinfunction "41_41") (pintype "bidirectional"))
    )
    (net (code "127") (name "unconnected-(U$1-Pad42)") (class "Default")
      (node (ref "U$1") (pin "42") (pinfunction "42_42") (pintype "bidirectional"))
    )
    (net (code "128") (name "unconnected-(U$1-Pad43)") (class "Default")
      (node (ref "U$1") (pin "43") (pinfunction "43_43") (pintype "bidirectional"))
    )
    (net (code "129") (name "unconnected-(U$1-Pad45)") (class "Default")
      (node (ref "U$1") (pin "45") (pinfunction "45_45") (pintype "bidirectional"))
    )
    (net (code "130") (name "unconnected-(U$1-PadA5)") (class "Default")
      (node (ref "U$1") (pin "A5") (pinfunction "A5_A5") (pintype "bidirectional"))
    )
    (net (code "131") (name "unconnected-(U$1-PadAREF)") (class "Default")
      (node (ref "U$1") (pin "AREF") (pinfunction "AREF_AREF") (pintype "bidirectional"))
    )
    (net (code "132") (name "unconnected-(U$1-PadCANRX)") (class "Default")
      (node (ref "U$1") (pin "CANRX") (pinfunction "CANRX_CANRX") (pintype "bidirectional"))
    )
    (net (code "133") (name "unconnected-(U$1-PadCANTX)") (class "Default")
      (node (ref "U$1") (pin "CANTX") (pinfunction "CANTX_CANTX") (pintype "bidirectional"))
    )
    (net (code "134") (name "unconnected-(U$1-PadDAC0)") (class "Default")
      (node (ref "U$1") (pin "DAC0") (pinfunction "DAC0_DAC0") (pintype "bidirectional"))
    )
    (net (code "135") (name "unconnected-(U$1-PadDAC1)") (class "Default")
      (node (ref "U$1") (pin "DAC1") (pinfunction "DAC1_DAC1") (pintype "bidirectional"))
    )
    (net (code "136") (name "unconnected-(U$1-PadGND1)") (class "Default")
      (node (ref "U$1") (pin "GND1") (pinfunction "GND1_GND1") (pintype "bidirectional"))
    )
    (net (code "137") (name "unconnected-(U$1-PadGND_A)") (class "Default")
      (node (ref "U$1") (pin "GND_A") (pinfunction "GND_A_GND_A") (pintype "bidirectional"))
    )
    (net (code "138") (name "unconnected-(U$1-PadGND_B)") (class "Default")
      (node (ref "U$1") (pin "GND_B") (pinfunction "GND_B_GND_B") (pintype "bidirectional"))
    )
    (net (code "139") (name "unconnected-(U$1-PadGND_DEBUG)") (class "Default")
      (node (ref "U$1") (pin "GND_DEBUG") (pinfunction "GND_DEBUG_GND_DEBUG") (pintype "bidirectional"))
    )
    (net (code "140") (name "unconnected-(U$1-PadGND_ICSP)") (class "Default")
      (node (ref "U$1") (pin "GND_ICSP") (pinfunction "GND_ICSP_GND_ICSP") (pintype "bidirectional"))
    )
    (net (code "141") (name "unconnected-(U$1-PadIOREF)") (class "Default")
      (node (ref "U$1") (pin "IOREF") (pinfunction "IOREF_IOREF") (pintype "bidirectional"))
    )
    (net (code "142") (name "unconnected-(U$1-PadNC)") (class "Default")
      (node (ref "U$1") (pin "NC") (pinfunction "NC_NC") (pintype "bidirectional"))
    )
    (net (code "143") (name "unconnected-(U$1-PadRESET)") (class "Default")
      (node (ref "U$1") (pin "RESET") (pinfunction "RESET_RESET") (pintype "bidirectional"))
    )
    (net (code "144") (name "unconnected-(U$1-PadRESET_DEBUG)") (class "Default")
      (node (ref "U$1") (pin "RESET_DEBUG") (pinfunction "RESET_DEBUG_RESET_DEBUG") (pintype "bidirectional"))
    )
    (net (code "145") (name "unconnected-(U$1-PadRESET_ICSP)") (class "Default")
      (node (ref "U$1") (pin "RESET_ICSP") (pinfunction "RESET_ICSP_RESET_ICSP") (pintype "bidirectional"))
    )
    (net (code "146") (name "unconnected-(U$1-PadRX1)") (class "Default")
      (node (ref "U$1") (pin "RX1") (pinfunction "RX1_RX1") (pintype "bidirectional"))
    )
    (net (code "147") (name "unconnected-(U$1-PadSCL)") (class "Default")
      (node (ref "U$1") (pin "SCL") (pinfunction "SCL_SCL") (pintype "bidirectional"))
    )
    (net (code "148") (name "unconnected-(U$1-PadSCL1)") (class "Default")
      (node (ref "U$1") (pin "SCL1") (pinfunction "SCL1_SCL1") (pintype "bidirectional"))
    )
    (net (code "149") (name "unconnected-(U$1-PadSDA)") (class "Default")
      (node (ref "U$1") (pin "SDA") (pinfunction "SDA_SDA") (pintype "bidirectional"))
    )
    (net (code "150") (name "unconnected-(U$1-PadSDA1)") (class "Default")
      (node (ref "U$1") (pin "SDA1") (pinfunction "SDA1_SDA1") (pintype "bidirectional"))
    )
    (net (code "151") (name "unconnected-(U$1-PadSWCLK_DEBUG)") (class "Default")
      (node (ref "U$1") (pin "SWCLK_DEBUG") (pinfunction "SWCLK_DEBUG_SWCLK_DEBUG") (pintype "bidirectional"))
    )
    (net (code "152") (name "unconnected-(U$1-PadSWDIO_DEBUG)") (class "Default")
      (node (ref "U$1") (pin "SWDIO_DEBUG") (pinfunction "SWDIO_DEBUG_SWDIO_DEBUG") (pintype "bidirectional"))
    )
    (net (code "153") (name "unconnected-(U$1-PadTX1)") (class "Default")
      (node (ref "U$1") (pin "TX1") (pinfunction "TX1_TX1") (pintype "bidirectional"))
    )
    (net (code "154") (name "unconnected-(U$5-EAOUT2-Pad6)") (class "Default")
      (node (ref "U$5") (pin "6") (pinfunction "EAOUT2_6") (pintype "bidirectional"))
    )
    (net (code "155") (name "unconnected-(U$5-NC2-Pad5)") (class "Default")
      (node (ref "U$5") (pin "5") (pinfunction "NC2_5") (pintype "bidirectional"))
    )
    (net (code "156") (name "unconnected-(U$5-REFOUT-Pad13)") (class "Default")
      (node (ref "U$5") (pin "13") (pinfunction "REFOUT_13") (pintype "bidirectional"))
    )
    (net (code "157") (name "unconnected-(U$5-REFOUT1-Pad4)") (class "Default")
      (node (ref "U$5") (pin "4") (pinfunction "REFOUT1_4") (pintype "bidirectional"))
    )
  )
)
